# esp32-thing.net
KiCad netlist of a schematic drawn in EAGLE
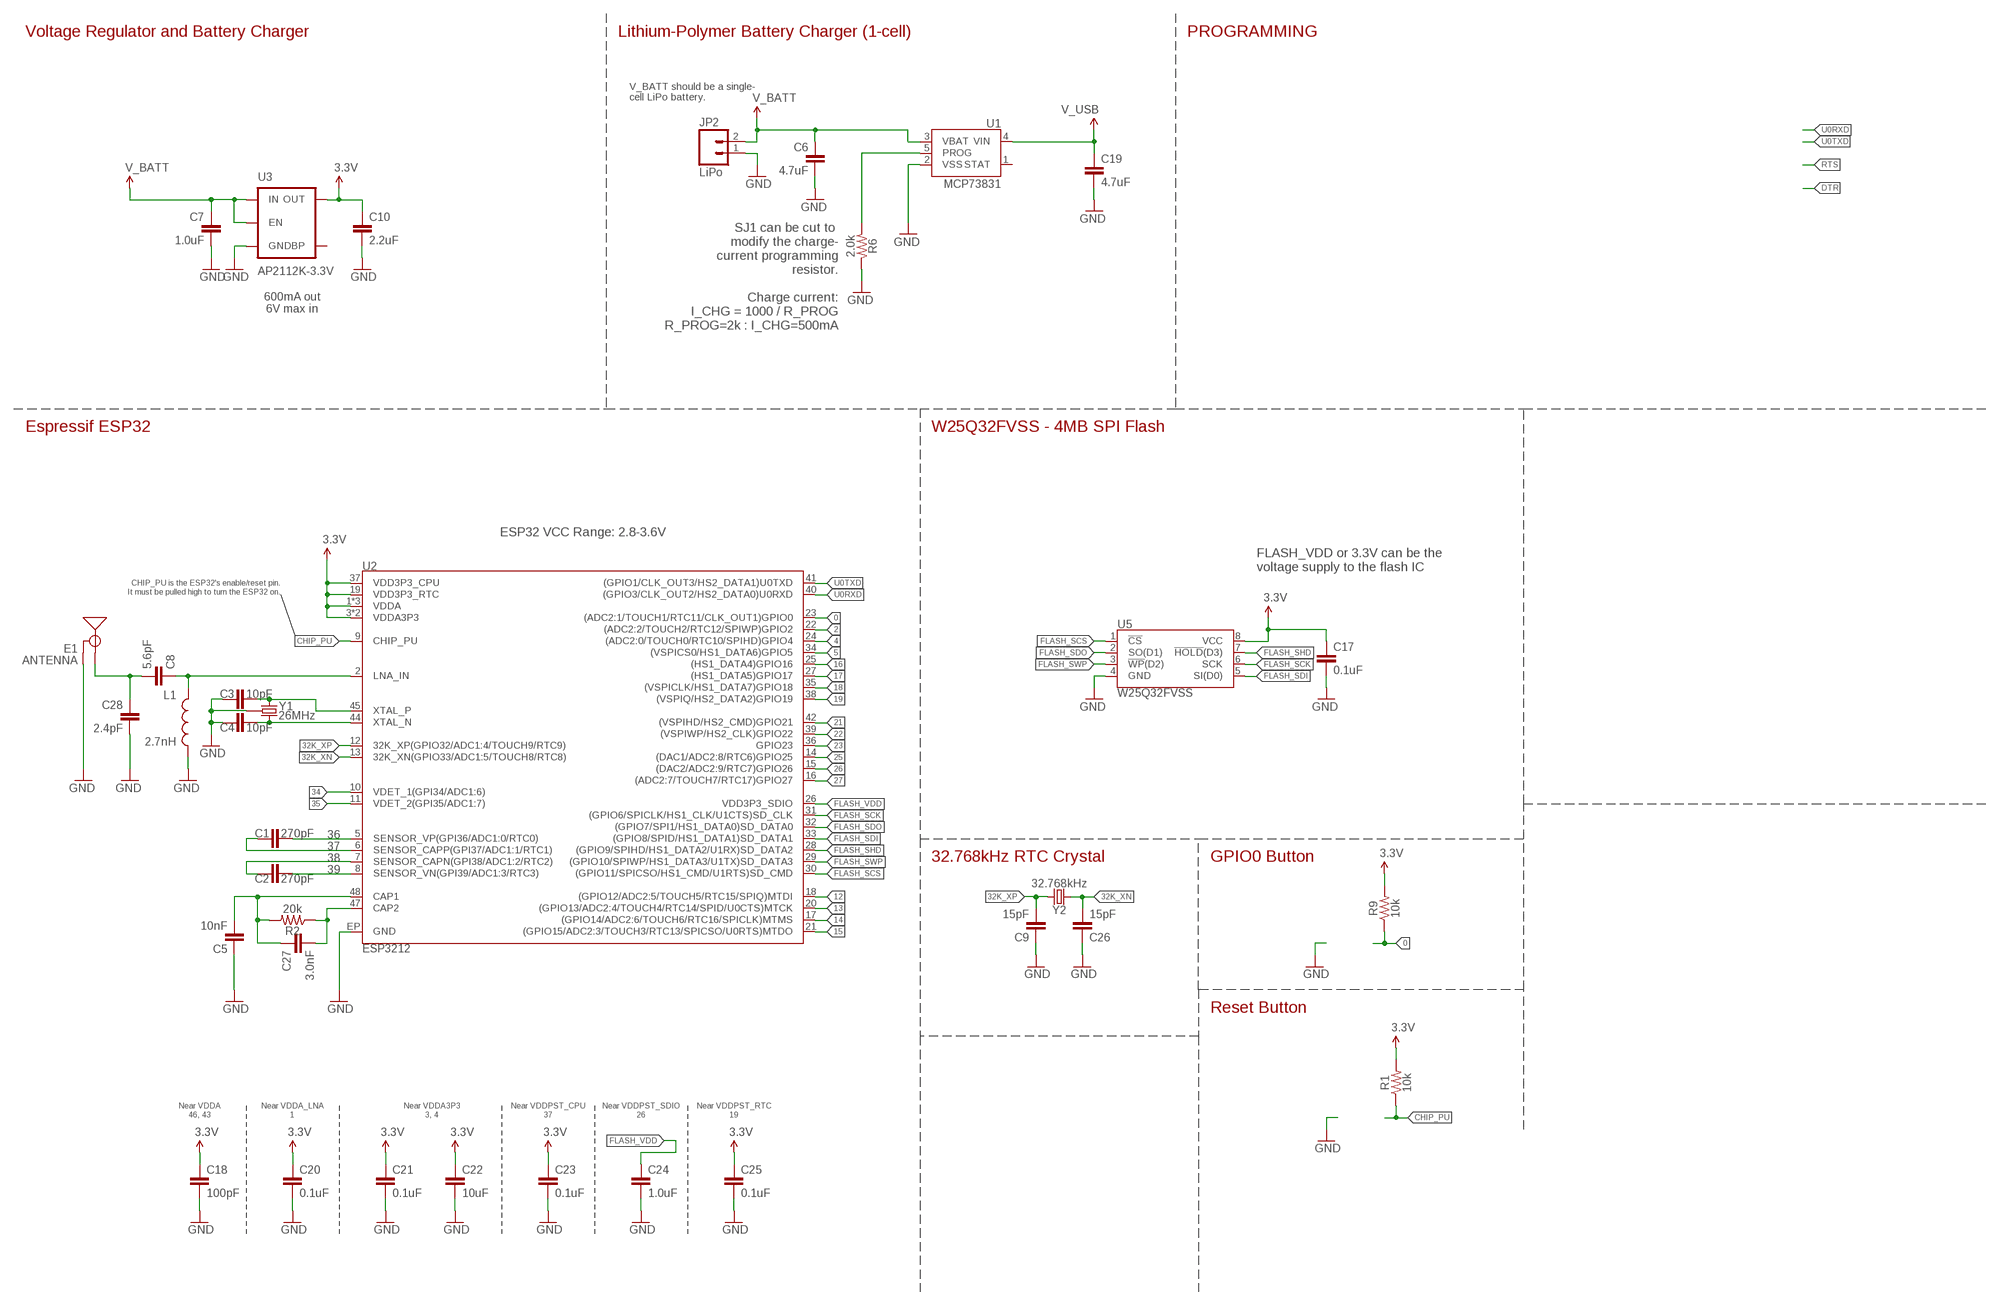
[diagram p0: schematic, sheet 1]

(export (version "E")
  (design (tool "Eeschema 10.0.6"))
  (components
    (comp (ref "C1")
      (value "270pF")
      (footprint "eagle-import:0603")
      (libsource (lib "eagle-import") (part "270PF-50V-5%(0603)"))
    )
    (comp (ref "C2")
      (value "270pF")
      (footprint "eagle-import:0603")
      (libsource (lib "eagle-import") (part "270PF-50V-5%(0603)"))
    )
    (comp (ref "C3")
      (value "10pF")
      (footprint "eagle-import:0603")
      (libsource (lib "eagle-import") (part "10PF-0603-50V-5%"))
    )
    (comp (ref "C4")
      (value "10pF")
      (footprint "eagle-import:0603")
      (libsource (lib "eagle-import") (part "10PF-0603-50V-5%"))
    )
    (comp (ref "C5")
      (value "10nF")
      (footprint "eagle-import:0603")
      (libsource (lib "eagle-import") (part "10NF-0603-50V-10%"))
    )
    (comp (ref "C6")
      (value "4.7uF")
      (footprint "eagle-import:0603")
      (libsource (lib "eagle-import") (part "4.7UF0603"))
    )
    (comp (ref "C7")
      (value "1.0uF")
      (footprint "eagle-import:0805")
      (libsource (lib "eagle-import") (part "1.0UF-0805-25V-(+80/-20%)"))
    )
    (comp (ref "C8")
      (value "5.6pF")
      (footprint "eagle-import:0603")
      (libsource (lib "eagle-import") (part "5.6PF-50V-5%(0603)"))
    )
    (comp (ref "C9")
      (value "15pF")
      (footprint "eagle-import:0603")
      (libsource (lib "eagle-import") (part "15PF-0603-50V-5%"))
    )
    (comp (ref "C10")
      (value "2.2uF")
      (footprint "eagle-import:0603")
      (libsource (lib "eagle-import") (part "2.2UF-0603-10V-20%"))
    )
    (comp (ref "C17")
      (value "0.1uF")
      (footprint "eagle-import:0603")
      (libsource (lib "eagle-import") (part "0.1UF-0603-25V-(+80/-20%)"))
    )
    (comp (ref "C18")
      (value "100pF")
      (footprint "eagle-import:0603")
      (libsource (lib "eagle-import") (part "100PF-0603-50V-5%"))
    )
    (comp (ref "C19")
      (value "4.7uF")
      (footprint "eagle-import:0603")
      (libsource (lib "eagle-import") (part "4.7UF0603"))
    )
    (comp (ref "C20")
      (value "0.1uF")
      (footprint "eagle-import:0603")
      (libsource (lib "eagle-import") (part "0.1UF-0603-25V-(+80/-20%)"))
    )
    (comp (ref "C21")
      (value "0.1uF")
      (footprint "eagle-import:0603")
      (libsource (lib "eagle-import") (part "0.1UF-0603-25V-(+80/-20%)"))
    )
    (comp (ref "C22")
      (value "10uF")
      (footprint "eagle-import:0603")
      (libsource (lib "eagle-import") (part "10UF-0603-6.3V-20%"))
    )
    (comp (ref "C23")
      (value "0.1uF")
      (footprint "eagle-import:0603")
      (libsource (lib "eagle-import") (part "0.1UF-0603-25V-(+80/-20%)"))
    )
    (comp (ref "C24")
      (value "1.0uF")
      (footprint "eagle-import:0603")
      (libsource (lib "eagle-import") (part "1.0UF-0603-16V-10%"))
    )
    (comp (ref "C25")
      (value "0.1uF")
      (footprint "eagle-import:0603")
      (libsource (lib "eagle-import") (part "0.1UF-0603-25V-(+80/-20%)"))
    )
    (comp (ref "C26")
      (value "15pF")
      (footprint "eagle-import:0603")
      (libsource (lib "eagle-import") (part "15PF-0603-50V-5%"))
    )
    (comp (ref "C27")
      (value "3.0nF")
      (footprint "eagle-import:0603")
      (libsource (lib "eagle-import") (part "3.0NF-0603-50V-5%"))
    )
    (comp (ref "C28")
      (value "2.4pF")
      (footprint "eagle-import:0603")
      (libsource (lib "eagle-import") (part "2.4PF-0603-50V-5%"))
    )
    (comp (ref "E1")
      (value "ANTENNA")
      (footprint "eagle-import:TRACE_ANTENNA_2.4GHZ_25.7MM_TUNED")
      (libsource (lib "eagle-import") (part "ANTENNATRACE-TUNED"))
    )
    (comp (ref "JP2")
      (value "LiPo")
      (footprint "eagle-import:JST-2-PTH")
      (libsource (lib "eagle-import") (part "M02JST-PTH-2"))
    )
    (comp (ref "L1")
      (value "2.7nH")
      (footprint "eagle-import:0603")
      (libsource (lib "eagle-import") (part "INDUCTOR0603"))
    )
    (comp (ref "R1")
      (value "10k")
      (footprint "eagle-import:0603")
      (libsource (lib "eagle-import") (part "10KOHM-1/10W-1%(0603)0603"))
    )
    (comp (ref "R2")
      (value "20k")
      (footprint "eagle-import:0603")
      (libsource (lib "eagle-import") (part "20KOHM-0603-1/10W-1%"))
    )
    (comp (ref "R6")
      (value "2.0k")
      (footprint "eagle-import:0603")
      (libsource (lib "eagle-import") (part "2.0KOHM1/10W5%(0603)"))
    )
    (comp (ref "R9")
      (value "10k")
      (footprint "eagle-import:0603")
      (libsource (lib "eagle-import") (part "10KOHM-1/10W-1%(0603)0603"))
    )
    (comp (ref "U1")
      (value "MCP73831")
      (footprint "eagle-import:SOT23-5")
      (libsource (lib "eagle-import") (part "MCP73831"))
    )
    (comp (ref "U2")
      (value "ESP3212")
      (footprint "eagle-import:QFN48-0.4MM")
      (libsource (lib "eagle-import") (part "ESP3212"))
    )
    (comp (ref "U3")
      (value "AP2112K-3.3V")
      (footprint "eagle-import:SOT23-5")
      (libsource (lib "eagle-import") (part "V_REG_LDOSMD"))
    )
    (comp (ref "U5")
      (value "W25Q32FVSS")
      (footprint "eagle-import:SOIC-8")
      (libsource (lib "eagle-import") (part "W25Q32FVSS"))
    )
    (comp (ref "Y1")
      (value "26MHz")
      (footprint "eagle-import:CRYSTAL-SMD-3.2X2.5")
      (libsource (lib "eagle-import") (part "CRYSTAL-GROUNDED3.2X2.5"))
    )
    (comp (ref "Y2")
      (value "32.768kHz")
      (footprint "eagle-import:CRYSTAL-SMD-3.2X1.5MM")
      (libsource (lib "eagle-import") (part "CRYSTAL-32.768KHZSMD-3.2X1.5"))
    )
  )
  (nets
    (net (code "1") (name "/36") (class "Default")
      (node (ref "C1") (pin "2") (pinfunction "2_2") (pintype "passive"))
      (node (ref "U2") (pin "5") (pinfunction "SENSOR_VP(GPI36/ADC1:0/RTC0)_5") (pintype "bidirectional"))
    )
    (net (code "2") (name "/37") (class "Default")
      (node (ref "C1") (pin "1") (pinfunction "1_1") (pintype "passive"))
      (node (ref "U2") (pin "6") (pinfunction "SENSOR_CAPP(GPI37/ADC1:1/RTC1)_6") (pintype "bidirectional"))
    )
    (net (code "3") (name "/38") (class "Default")
      (node (ref "C2") (pin "1") (pinfunction "1_1") (pintype "passive"))
      (node (ref "U2") (pin "7") (pinfunction "SENSOR_CAPN(GPI38/ADC1:2/RTC2)_7") (pintype "bidirectional"))
    )
    (net (code "4") (name "/39") (class "Default")
      (node (ref "C2") (pin "2") (pinfunction "2_2") (pintype "passive"))
      (node (ref "U2") (pin "8") (pinfunction "SENSOR_VN(GPI39/ADC1:3/RTC3)_8") (pintype "bidirectional"))
    )
    (net (code "5") (name "0") (class "Default")
      (node (ref "R9") (pin "1") (pinfunction "1_1") (pintype "passive"))
      (node (ref "U2") (pin "23") (pinfunction "(ADC2:1/TOUCH1/RTC11/CLK_OUT1)GPIO0_23") (pintype "bidirectional"))
    )
    (net (code "6") (name "2") (class "Default")
      (node (ref "U2") (pin "22") (pinfunction "(ADC2:2/TOUCH2/RTC12/SPIWP)GPIO2_22") (pintype "bidirectional"))
    )
    (net (code "7") (name "3.3V") (class "Default")
      (node (ref "C10") (pin "1") (pinfunction "1_1") (pintype "passive"))
      (node (ref "C17") (pin "1") (pinfunction "1_1") (pintype "passive"))
      (node (ref "C18") (pin "1") (pinfunction "1_1") (pintype "passive"))
      (node (ref "C20") (pin "1") (pinfunction "1_1") (pintype "passive"))
      (node (ref "C21") (pin "1") (pinfunction "1_1") (pintype "passive"))
      (node (ref "C22") (pin "1") (pinfunction "1_1") (pintype "passive"))
      (node (ref "C23") (pin "1") (pinfunction "1_1") (pintype "passive"))
      (node (ref "C25") (pin "1") (pinfunction "1_1") (pintype "passive"))
      (node (ref "R1") (pin "2") (pinfunction "2_2") (pintype "passive"))
      (node (ref "R9") (pin "2") (pinfunction "2_2") (pintype "passive"))
      (node (ref "U2") (pin "1") (pinfunction "VDDA_1") (pintype "bidirectional"))
      (node (ref "U2") (pin "19") (pinfunction "VDD3P3_RTC_19") (pintype "bidirectional"))
      (node (ref "U2") (pin "3") (pinfunction "VDDA3P3_3") (pintype "bidirectional"))
      (node (ref "U2") (pin "37") (pinfunction "VDD3P3_CPU_37") (pintype "bidirectional"))
      (node (ref "U2") (pin "4") (pinfunction "VDDA3P3_4") (pintype "bidirectional"))
      (node (ref "U2") (pin "43") (pinfunction "VDDA_43") (pintype "bidirectional"))
      (node (ref "U2") (pin "46") (pinfunction "VDDA_46") (pintype "bidirectional"))
      (node (ref "U3") (pin "5") (pinfunction "OUT_5") (pintype "passive"))
      (node (ref "U5") (pin "8") (pinfunction "VCC_8") (pintype "bidirectional"))
    )
    (net (code "8") (name "4") (class "Default")
      (node (ref "U2") (pin "24") (pinfunction "(ADC2:0/TOUCH0/RTC10/SPIHD)GPIO4_24") (pintype "bidirectional"))
    )
    (net (code "9") (name "5") (class "Default")
      (node (ref "U2") (pin "34") (pinfunction "(VSPICS0/HS1_DATA6)GPIO5_34") (pintype "bidirectional"))
    )
    (net (code "10") (name "12") (class "Default")
      (node (ref "U2") (pin "18") (pinfunction "(GPIO12/ADC2:5/TOUCH5/RTC15/SPIQ)MTDI_18") (pintype "bidirectional"))
    )
    (net (code "11") (name "13") (class "Default")
      (node (ref "U2") (pin "20") (pinfunction "(GPIO13/ADC2:4/TOUCH4/RTC14/SPID/U0CTS)MTCK_20") (pintype "bidirectional"))
    )
    (net (code "12") (name "14") (class "Default")
      (node (ref "U2") (pin "17") (pinfunction "(GPIO14/ADC2:6/TOUCH6/RTC16/SPICLK)MTMS_17") (pintype "bidirectional"))
    )
    (net (code "13") (name "15") (class "Default")
      (node (ref "U2") (pin "21") (pinfunction "(GPIO15/ADC2:3/TOUCH3/RTC13/SPICSO/U0RTS)MTDO_21") (pintype "bidirectional"))
    )
    (net (code "14") (name "16") (class "Default")
      (node (ref "U2") (pin "25") (pinfunction "(HS1_DATA4)GPIO16_25") (pintype "bidirectional"))
    )
    (net (code "15") (name "17") (class "Default")
      (node (ref "U2") (pin "27") (pinfunction "(HS1_DATA5)GPIO17_27") (pintype "bidirectional"))
    )
    (net (code "16") (name "18") (class "Default")
      (node (ref "U2") (pin "35") (pinfunction "(VSPICLK/HS1_DATA7)GPIO18_35") (pintype "bidirectional"))
    )
    (net (code "17") (name "19") (class "Default")
      (node (ref "U2") (pin "38") (pinfunction "(VSPIQ/HS2_DATA2)GPIO19_38") (pintype "bidirectional"))
    )
    (net (code "18") (name "21") (class "Default")
      (node (ref "U2") (pin "42") (pinfunction "(VSPIHD/HS2_CMD)GPIO21_42") (pintype "bidirectional"))
    )
    (net (code "19") (name "22") (class "Default")
      (node (ref "U2") (pin "39") (pinfunction "(VSPIWP/HS2_CLK)GPIO22_39") (pintype "bidirectional"))
    )
    (net (code "20") (name "23") (class "Default")
      (node (ref "U2") (pin "36") (pinfunction "GPIO23_36") (pintype "bidirectional"))
    )
    (net (code "21") (name "25") (class "Default")
      (node (ref "U2") (pin "14") (pinfunction "(DAC1/ADC2:8/RTC6)GPIO25_14") (pintype "bidirectional"))
    )
    (net (code "22") (name "26") (class "Default")
      (node (ref "U2") (pin "15") (pinfunction "(DAC2/ADC2:9/RTC7)GPIO26_15") (pintype "bidirectional"))
    )
    (net (code "23") (name "27") (class "Default")
      (node (ref "U2") (pin "16") (pinfunction "(ADC2:7/TOUCH7/RTC17)GPIO27_16") (pintype "bidirectional"))
    )
    (net (code "24") (name "32K_XN") (class "Default")
      (node (ref "C26") (pin "2") (pinfunction "2_2") (pintype "passive"))
      (node (ref "U2") (pin "13") (pinfunction "32K_XN(GPIO33/ADC1:5/TOUCH8/RTC8)_13") (pintype "bidirectional"))
      (node (ref "Y2") (pin "P$2") (pinfunction "2_P$2") (pintype "passive"))
    )
    (net (code "25") (name "32K_XP") (class "Default")
      (node (ref "C9") (pin "2") (pinfunction "2_2") (pintype "passive"))
      (node (ref "U2") (pin "12") (pinfunction "32K_XP(GPIO32/ADC1:4/TOUCH9/RTC9)_12") (pintype "bidirectional"))
      (node (ref "Y2") (pin "P$1") (pinfunction "1_P$1") (pintype "passive"))
    )
    (net (code "26") (name "34") (class "Default")
      (node (ref "U2") (pin "10") (pinfunction "VDET_1(GPI34/ADC1:6)_10") (pintype "bidirectional"))
    )
    (net (code "27") (name "35") (class "Default")
      (node (ref "U2") (pin "11") (pinfunction "VDET_2(GPI35/ADC1:7)_11") (pintype "bidirectional"))
    )
    (net (code "28") (name "CHIP_PU") (class "Default")
      (node (ref "R1") (pin "1") (pinfunction "1_1") (pintype "passive"))
      (node (ref "U2") (pin "9") (pinfunction "CHIP_PU_9") (pintype "bidirectional"))
    )
    (net (code "30") (name "FLASH_SCK") (class "Default")
      (node (ref "U2") (pin "31") (pinfunction "(GPIO6/SPICLK/HS1_CLK/U1CTS)SD_CLK_31") (pintype "bidirectional"))
      (node (ref "U5") (pin "6") (pinfunction "SCK_6") (pintype "bidirectional"))
    )
    (net (code "31") (name "FLASH_SCS") (class "Default")
      (node (ref "U2") (pin "30") (pinfunction "(GPIO11/SPICSO/HS1_CMD/U1RTS)SD_CMD_30") (pintype "bidirectional"))
      (node (ref "U5") (pin "1") (pinfunction "~{CS}_1") (pintype "bidirectional"))
    )
    (net (code "32") (name "FLASH_SDI") (class "Default")
      (node (ref "U2") (pin "33") (pinfunction "(GPIO8/SPID/HS1_DATA1)SD_DATA1_33") (pintype "bidirectional"))
      (node (ref "U5") (pin "5") (pinfunction "SI(D0)_5") (pintype "bidirectional"))
    )
    (net (code "33") (name "FLASH_SDO") (class "Default")
      (node (ref "U2") (pin "32") (pinfunction "(GPIO7/SPI1/HS1_DATA0)SD_DATA0_32") (pintype "bidirectional"))
      (node (ref "U5") (pin "2") (pinfunction "SO(D1)_2") (pintype "bidirectional"))
    )
    (net (code "34") (name "FLASH_SHD") (class "Default")
      (node (ref "U2") (pin "28") (pinfunction "(GPIO9/SPIHD/HS1_DATA2/U1RX)SD_DATA2_28") (pintype "bidirectional"))
      (node (ref "U5") (pin "7") (pinfunction "~{HOLD}(D3)_7") (pintype "bidirectional"))
    )
    (net (code "35") (name "FLASH_SWP") (class "Default")
      (node (ref "U2") (pin "29") (pinfunction "(GPIO10/SPIWP/HS1_DATA3/U1TX)SD_DATA3_29") (pintype "bidirectional"))
      (node (ref "U5") (pin "3") (pinfunction "~{WP}(D2)_3") (pintype "bidirectional"))
    )
    (net (code "36") (name "FLASH_VDD") (class "Default")
      (node (ref "C24") (pin "1") (pinfunction "1_1") (pintype "passive"))
      (node (ref "U2") (pin "26") (pinfunction "VDD3P3_SDIO_26") (pintype "bidirectional"))
    )
    (net (code "37") (name "GND") (class "Default")
      (node (ref "C10") (pin "2") (pinfunction "2_2") (pintype "passive"))
      (node (ref "C17") (pin "2") (pinfunction "2_2") (pintype "passive"))
      (node (ref "C18") (pin "2") (pinfunction "2_2") (pintype "passive"))
      (node (ref "C19") (pin "2") (pinfunction "2_2") (pintype "passive"))
      (node (ref "C20") (pin "2") (pinfunction "2_2") (pintype "passive"))
      (node (ref "C21") (pin "2") (pinfunction "2_2") (pintype "passive"))
      (node (ref "C22") (pin "2") (pinfunction "2_2") (pintype "passive"))
      (node (ref "C23") (pin "2") (pinfunction "2_2") (pintype "passive"))
      (node (ref "C24") (pin "2") (pinfunction "2_2") (pintype "passive"))
      (node (ref "C25") (pin "2") (pinfunction "2_2") (pintype "passive"))
      (node (ref "C26") (pin "1") (pinfunction "1_1") (pintype "passive"))
      (node (ref "C28") (pin "2") (pinfunction "2_2") (pintype "passive"))
      (node (ref "C3") (pin "1") (pinfunction "1_1") (pintype "passive"))
      (node (ref "C4") (pin "1") (pinfunction "1_1") (pintype "passive"))
      (node (ref "C5") (pin "1") (pinfunction "1_1") (pintype "passive"))
      (node (ref "C6") (pin "2") (pinfunction "2_2") (pintype "passive"))
      (node (ref "C7") (pin "2") (pinfunction "2_2") (pintype "passive"))
      (node (ref "C9") (pin "1") (pinfunction "1_1") (pintype "passive"))
      (node (ref "E1") (pin "GND") (pinfunction "GND_GND") (pintype "bidirectional"))
      (node (ref "E1") (pin "GND2") (pinfunction "GND_GND2") (pintype "bidirectional"))
      (node (ref "JP2") (pin "1") (pinfunction "1_1") (pintype "passive"))
      (node (ref "L1") (pin "2") (pinfunction "2_2") (pintype "passive"))
      (node (ref "R6") (pin "1") (pinfunction "1_1") (pintype "passive"))
      (node (ref "U1") (pin "2") (pinfunction "VSS_2") (pintype "power_in"))
      (node (ref "U2") (pin "EP") (pinfunction "GND_EP") (pintype "bidirectional"))
      (node (ref "U3") (pin "2") (pinfunction "GND_2") (pintype "input"))
      (node (ref "U5") (pin "4") (pinfunction "GND_4") (pintype "bidirectional"))
      (node (ref "Y1") (pin "2") (pinfunction "GND_2") (pintype "passive"))
      (node (ref "Y1") (pin "4") (pinfunction "GND_4") (pintype "passive"))
    )
    (net (code "38") (name "Net-(E1-SIGNAL)") (class "Default")
      (node (ref "C28") (pin "1") (pinfunction "1_1") (pintype "passive"))
      (node (ref "C8") (pin "2") (pinfunction "2_2") (pintype "passive"))
      (node (ref "E1") (pin "ANT") (pinfunction "SIGNAL_ANT") (pintype "bidirectional"))
    )
    (net (code "39") (name "Net-(U1-PROG)") (class "Default")
      (node (ref "R6") (pin "2") (pinfunction "2_2") (pintype "passive"))
      (node (ref "U1") (pin "5") (pinfunction "PROG_5") (pintype "input"))
    )
    (net (code "40") (name "Net-(U2-CAP1)") (class "Default")
      (node (ref "C27") (pin "1") (pinfunction "1_1") (pintype "passive"))
      (node (ref "C5") (pin "2") (pinfunction "2_2") (pintype "passive"))
      (node (ref "R2") (pin "2") (pinfunction "2_2") (pintype "passive"))
      (node (ref "U2") (pin "48") (pinfunction "CAP1_48") (pintype "bidirectional"))
    )
    (net (code "41") (name "Net-(U2-CAP2)") (class "Default")
      (node (ref "C27") (pin "2") (pinfunction "2_2") (pintype "passive"))
      (node (ref "R2") (pin "1") (pinfunction "1_1") (pintype "passive"))
      (node (ref "U2") (pin "47") (pinfunction "CAP2_47") (pintype "bidirectional"))
    )
    (net (code "42") (name "Net-(U2-LNA_IN)") (class "Default")
      (node (ref "C8") (pin "1") (pinfunction "1_1") (pintype "passive"))
      (node (ref "L1") (pin "1") (pinfunction "1_1") (pintype "passive"))
      (node (ref "U2") (pin "2") (pinfunction "LNA_IN_2") (pintype "bidirectional"))
    )
    (net (code "43") (name "Net-(U2-XTAL_N)") (class "Default")
      (node (ref "C4") (pin "2") (pinfunction "2_2") (pintype "passive"))
      (node (ref "U2") (pin "44") (pinfunction "XTAL_N_44") (pintype "bidirectional"))
      (node (ref "Y1") (pin "3") (pinfunction "2_3") (pintype "passive"))
    )
    (net (code "44") (name "Net-(U2-XTAL_P)") (class "Default")
      (node (ref "C3") (pin "2") (pinfunction "2_2") (pintype "passive"))
      (node (ref "U2") (pin "45") (pinfunction "XTAL_P_45") (pintype "bidirectional"))
      (node (ref "Y1") (pin "1") (pinfunction "1_1") (pintype "passive"))
    )
    (net (code "46") (name "U0RXD") (class "Default")
      (node (ref "U2") (pin "40") (pinfunction "(GPIO3/CLK_OUT2/HS2_DATA0)U0RXD_40") (pintype "bidirectional"))
    )
    (net (code "47") (name "U0TXD") (class "Default")
      (node (ref "U2") (pin "41") (pinfunction "(GPIO1/CLK_OUT3/HS2_DATA1)U0TXD_41") (pintype "bidirectional"))
    )
    (net (code "48") (name "V_BATT") (class "Default")
      (node (ref "C6") (pin "1") (pinfunction "1_1") (pintype "passive"))
      (node (ref "C7") (pin "1") (pinfunction "1_1") (pintype "passive"))
      (node (ref "JP2") (pin "2") (pinfunction "2_2") (pintype "passive"))
      (node (ref "U1") (pin "3") (pinfunction "VBAT_3") (pintype "power_in"))
      (node (ref "U3") (pin "1") (pinfunction "IN_1") (pintype "input"))
      (node (ref "U3") (pin "3") (pinfunction "EN_3") (pintype "input"))
    )
    (net (code "49") (name "V_USB") (class "Default")
      (node (ref "C19") (pin "1") (pinfunction "1_1") (pintype "passive"))
      (node (ref "U1") (pin "4") (pinfunction "VIN_4") (pintype "power_in"))
    )
    (net (code "50") (name "unconnected-(U1-STAT-Pad1)") (class "Default")
      (node (ref "U1") (pin "1") (pinfunction "STAT_1") (pintype "output"))
    )
    (net (code "51") (name "unconnected-(U3-BP-Pad4)") (class "Default")
      (node (ref "U3") (pin "4") (pinfunction "BP_4") (pintype "input"))
    )
  )
)
